# Adafruit_MiniLipo.net
KiCad netlist of a schematic drawn in EAGLE
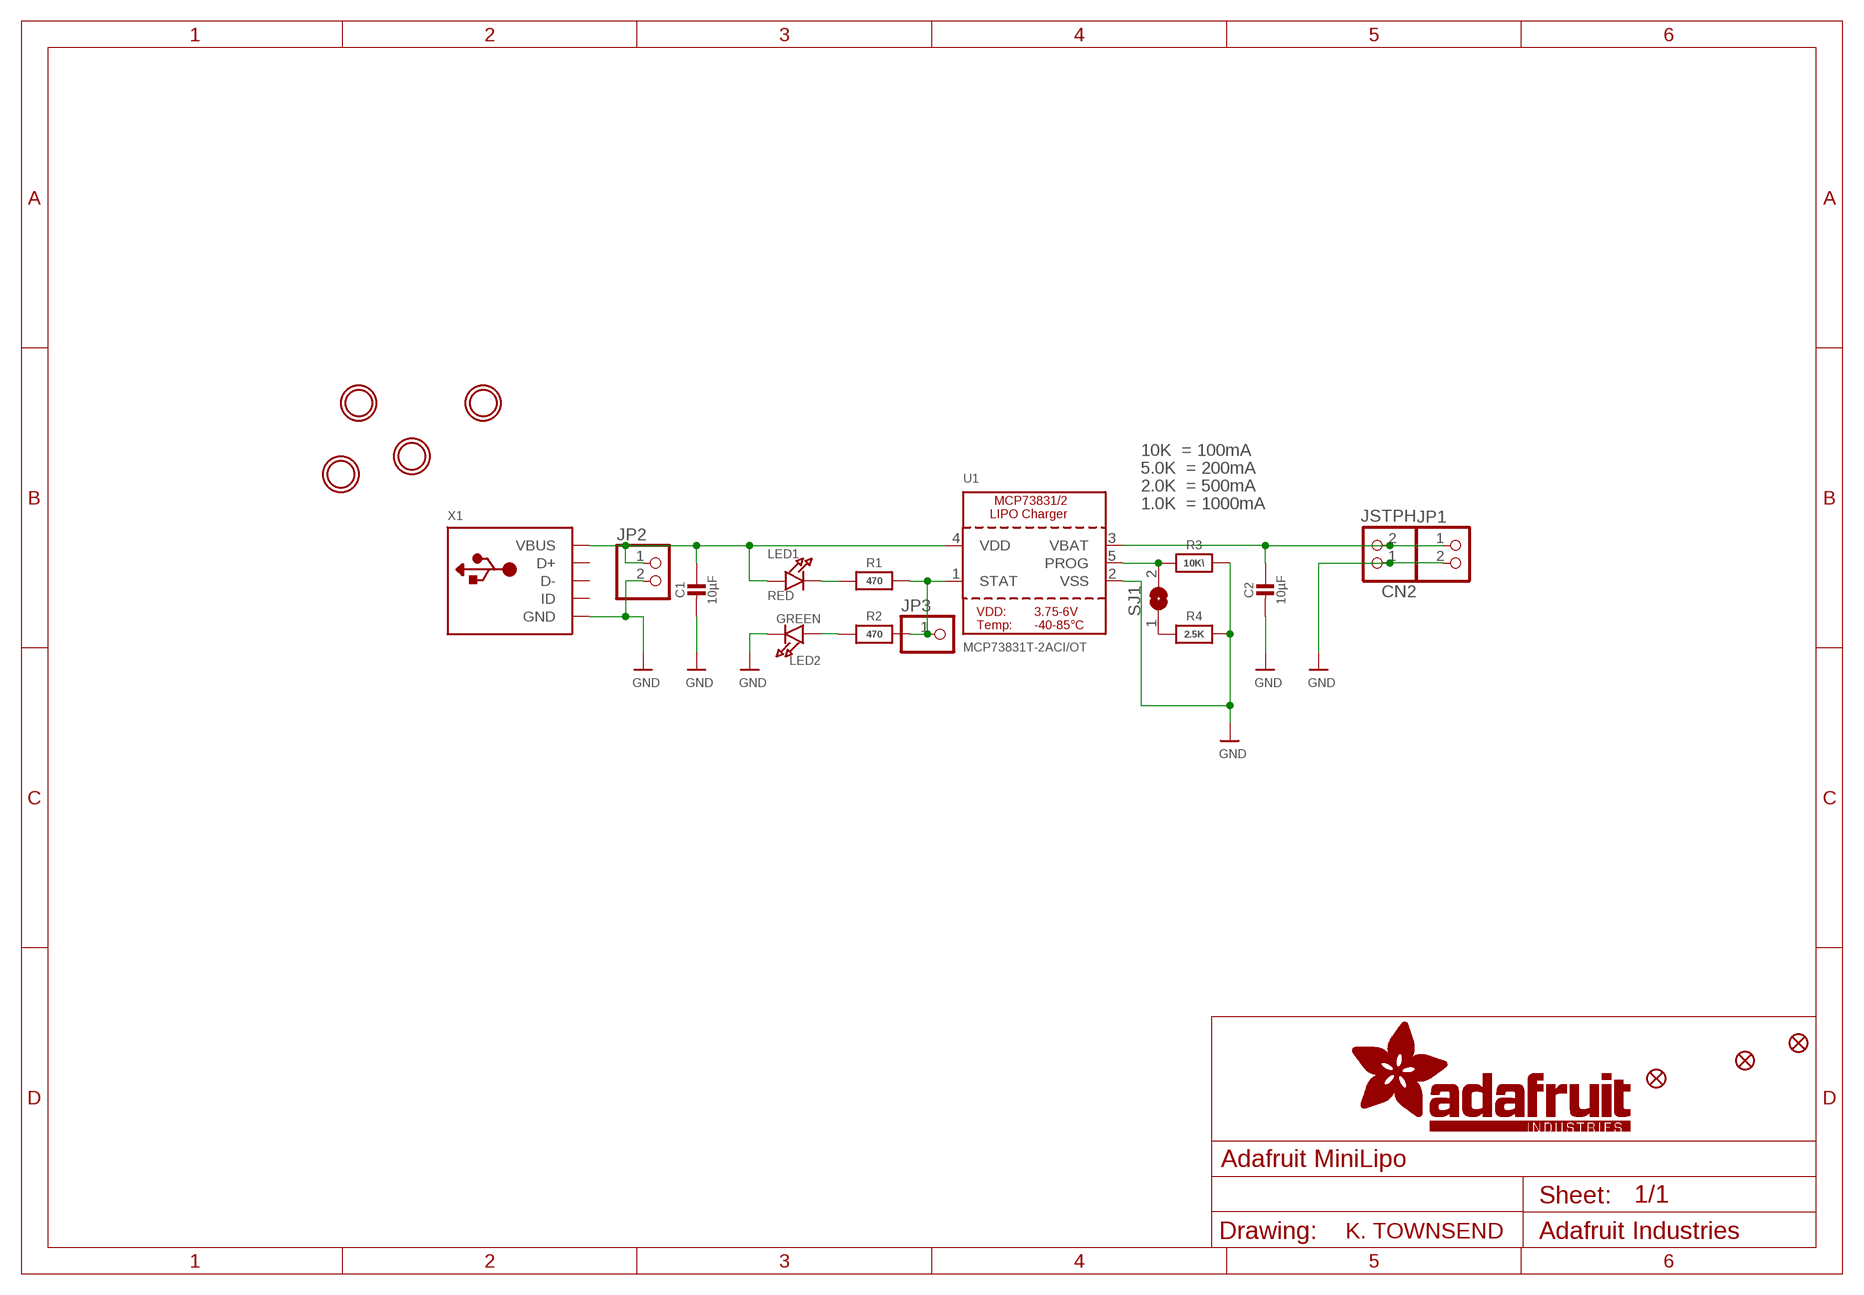
[diagram p0: schematic, sheet 1]

(export (version "E")
  (design (tool "Eeschema 10.0.6"))
  (components
    (comp (ref "C1")
      (value "10µF")
      (footprint "eagle-import:0805-NO")
      (libsource (lib "eagle-import") (part "CAP_CERAMIC0805-NOOUTLINE"))
    )
    (comp (ref "C2")
      (value "10µF")
      (footprint "eagle-import:0805-NO")
      (libsource (lib "eagle-import") (part "CAP_CERAMIC0805-NOOUTLINE"))
    )
    (comp (ref "CN2")
      (value "JSTPH")
      (footprint "eagle-import:JSTPH2")
      (libsource (lib "eagle-import") (part "JST_2PIN"))
    )
    (comp (ref "FID1")
      (value "FIDUCIAL\"\"")
      (footprint "eagle-import:FIDUCIAL_1MM")
      (libsource (lib "eagle-import") (part "FIDUCIAL{dblquote}{dblquote}"))
    )
    (comp (ref "FID2")
      (value "FIDUCIAL\"\"")
      (footprint "eagle-import:FIDUCIAL_1MM")
      (fields (field (name "BOM") "EXCLUDE"))
      (libsource (lib "eagle-import") (part "FIDUCIAL{dblquote}{dblquote}"))
    )
    (comp (ref "FID3")
      (value "FIDUCIAL\"\"")
      (footprint "eagle-import:FIDUCIAL_1MM")
      (fields (field (name "BOM") "EXCLUDE"))
      (libsource (lib "eagle-import") (part "FIDUCIAL{dblquote}{dblquote}"))
    )
    (comp (ref "JP1")
      (value "HEADER-1X2ROUND")
      (footprint "eagle-import:1X02_ROUND")
      (libsource (lib "eagle-import") (part "HEADER-1X2ROUND"))
    )
    (comp (ref "JP2")
      (value "HEADER-1X2ROUND")
      (footprint "eagle-import:1X02_ROUND")
      (libsource (lib "eagle-import") (part "HEADER-1X2ROUND"))
    )
    (comp (ref "JP3")
      (value "PINHD-1X1CB")
      (footprint "eagle-import:1X01-CLEANBIG")
      (libsource (lib "eagle-import") (part "PINHD-1X1CB"))
    )
    (comp (ref "LED1")
      (value "RED")
      (footprint "eagle-import:CHIPLED_0805_NOOUTLINE")
      (libsource (lib "eagle-import") (part "LED0805_NOOUTLINE"))
    )
    (comp (ref "LED2")
      (value "GREEN")
      (footprint "eagle-import:CHIPLED_0805_NOOUTLINE")
      (libsource (lib "eagle-import") (part "LED0805_NOOUTLINE"))
    )
    (comp (ref "R1")
      (value "470")
      (footprint "eagle-import:0805-NO")
      (libsource (lib "eagle-import") (part "RESISTOR0805_NOOUTLINE"))
    )
    (comp (ref "R2")
      (value "470")
      (footprint "eagle-import:0805-NO")
      (libsource (lib "eagle-import") (part "RESISTOR0805_NOOUTLINE"))
    )
    (comp (ref "R3")
      (value "10K\\")
      (footprint "eagle-import:0805-NO")
      (libsource (lib "eagle-import") (part "RESISTOR0805_NOOUTLINE"))
    )
    (comp (ref "R4")
      (value "2.5K")
      (footprint "eagle-import:0805-NO")
      (libsource (lib "eagle-import") (part "RESISTOR0805_NOOUTLINE"))
    )
    (comp (ref "SJ1")
      (value "SOLDERJUMPER")
      (footprint "eagle-import:SOLDERJUMPER_ARROW_NOPASTE")
      (libsource (lib "eagle-import") (part "SOLDERJUMPER"))
    )
    (comp (ref "U$9")
      (value "MOUNTINGHOLE2.5")
      (footprint "eagle-import:MOUNTINGHOLE_2.5_PLATED")
      (libsource (lib "eagle-import") (part "MOUNTINGHOLE2.5"))
    )
    (comp (ref "U$10")
      (value "MOUNTINGHOLE2.5")
      (footprint "eagle-import:MOUNTINGHOLE_2.5_PLATED")
      (libsource (lib "eagle-import") (part "MOUNTINGHOLE2.5"))
    )
    (comp (ref "U$11")
      (value "MOUNTINGHOLE2.5")
      (footprint "eagle-import:MOUNTINGHOLE_2.5_PLATED")
      (libsource (lib "eagle-import") (part "MOUNTINGHOLE2.5"))
    )
    (comp (ref "U$12")
      (value "MOUNTINGHOLE2.5")
      (footprint "eagle-import:MOUNTINGHOLE_2.5_PLATED")
      (libsource (lib "eagle-import") (part "MOUNTINGHOLE2.5"))
    )
    (comp (ref "U1")
      (value "MCP73831T-2ACI/OT")
      (footprint "eagle-import:SOT23-5")
      (libsource (lib "eagle-import") (part "MCP73831/2"))
    )
    (comp (ref "X1")
      (value "USB_MEDIUM")
      (footprint "eagle-import:USB-MINI_MEDIUM")
      (libsource (lib "eagle-import") (part "USB_MEDIUM"))
    )
  )
  (nets
    (net (code "1") (name "GND") (class "Default")
      (node (ref "C1") (pin "2") (pinfunction "2_2") (pintype "passive"))
      (node (ref "C2") (pin "2") (pinfunction "2_2") (pintype "passive"))
      (node (ref "CN2") (pin "1") (pinfunction "1_1") (pintype "passive"))
      (node (ref "JP1") (pin "2") (pinfunction "2_2") (pintype "passive"))
      (node (ref "JP2") (pin "2") (pinfunction "2_2") (pintype "passive"))
      (node (ref "LED2") (pin "C") (pinfunction "C_C") (pintype "passive"))
      (node (ref "R3") (pin "2") (pinfunction "2_2") (pintype "passive"))
      (node (ref "R4") (pin "2") (pinfunction "2_2") (pintype "passive"))
      (node (ref "U1") (pin "2") (pinfunction "VSS_2") (pintype "power_in"))
      (node (ref "X1") (pin "GND") (pinfunction "GND_GND") (pintype "power_in"))
      (node (ref "X1") (pin "GND1") (pinfunction "GND_GND1") (pintype "power_in"))
      (node (ref "X1") (pin "GND2") (pinfunction "GND_GND2") (pintype "power_in"))
      (node (ref "X1") (pin "GND3") (pinfunction "GND_GND3") (pintype "power_in"))
      (node (ref "X1") (pin "GND4") (pinfunction "GND_GND4") (pintype "power_in"))
    )
    (net (code "2") (name "Net-(LED1-PadC)") (class "Default")
      (node (ref "LED1") (pin "C") (pinfunction "C_C") (pintype "passive"))
      (node (ref "R1") (pin "1") (pinfunction "1_1") (pintype "passive"))
    )
    (net (code "3") (name "Net-(LED2-PadA)") (class "Default")
      (node (ref "LED2") (pin "A") (pinfunction "A_A") (pintype "passive"))
      (node (ref "R2") (pin "1") (pinfunction "1_1") (pintype "passive"))
    )
    (net (code "4") (name "Net-(R4-Pad1)") (class "Default")
      (node (ref "R4") (pin "1") (pinfunction "1_1") (pintype "passive"))
      (node (ref "SJ1") (pin "1") (pinfunction "1_1") (pintype "passive"))
    )
    (net (code "5") (name "Net-(U1-PROG)") (class "Default")
      (node (ref "R3") (pin "1") (pinfunction "1_1") (pintype "passive"))
      (node (ref "SJ1") (pin "2") (pinfunction "2_2") (pintype "passive"))
      (node (ref "U1") (pin "5") (pinfunction "PROG_5") (pintype "input"))
    )
    (net (code "6") (name "Net-(U1-STAT)") (class "Default")
      (node (ref "JP3") (pin "1") (pinfunction "1_1") (pintype "passive"))
      (node (ref "R1") (pin "2") (pinfunction "2_2") (pintype "passive"))
      (node (ref "R2") (pin "2") (pinfunction "2_2") (pintype "passive"))
      (node (ref "U1") (pin "1") (pinfunction "STAT_1") (pintype "output"))
    )
    (net (code "7") (name "Net-(U1-VBAT)") (class "Default")
      (node (ref "C2") (pin "1") (pinfunction "1_1") (pintype "passive"))
      (node (ref "CN2") (pin "2") (pinfunction "2_2") (pintype "passive"))
      (node (ref "JP1") (pin "1") (pinfunction "1_1") (pintype "passive"))
      (node (ref "U1") (pin "3") (pinfunction "VBAT_3") (pintype "power_in"))
    )
    (net (code "8") (name "Net-(U1-VDD)") (class "Default")
      (node (ref "C1") (pin "1") (pinfunction "1_1") (pintype "passive"))
      (node (ref "JP2") (pin "1") (pinfunction "1_1") (pintype "passive"))
      (node (ref "LED1") (pin "A") (pinfunction "A_A") (pintype "passive"))
      (node (ref "U1") (pin "4") (pinfunction "VDD_4") (pintype "power_in"))
      (node (ref "X1") (pin "VBUS") (pinfunction "VBUS_VBUS") (pintype "power_in"))
    )
    (net (code "9") (name "unconnected-(X1-PadD+)") (class "Default")
      (node (ref "X1") (pin "D+") (pinfunction "D+_D+") (pintype "bidirectional"))
    )
    (net (code "10") (name "unconnected-(X1-PadD-)") (class "Default")
      (node (ref "X1") (pin "D-") (pinfunction "D-_D-") (pintype "bidirectional"))
    )
    (net (code "11") (name "unconnected-(X1-PadID)") (class "Default")
      (node (ref "X1") (pin "ID") (pinfunction "ID_ID") (pintype "bidirectional"))
    )
  )
)
